# Qwiic_Power_Switch.net
KiCad netlist of a schematic drawn in EAGLE
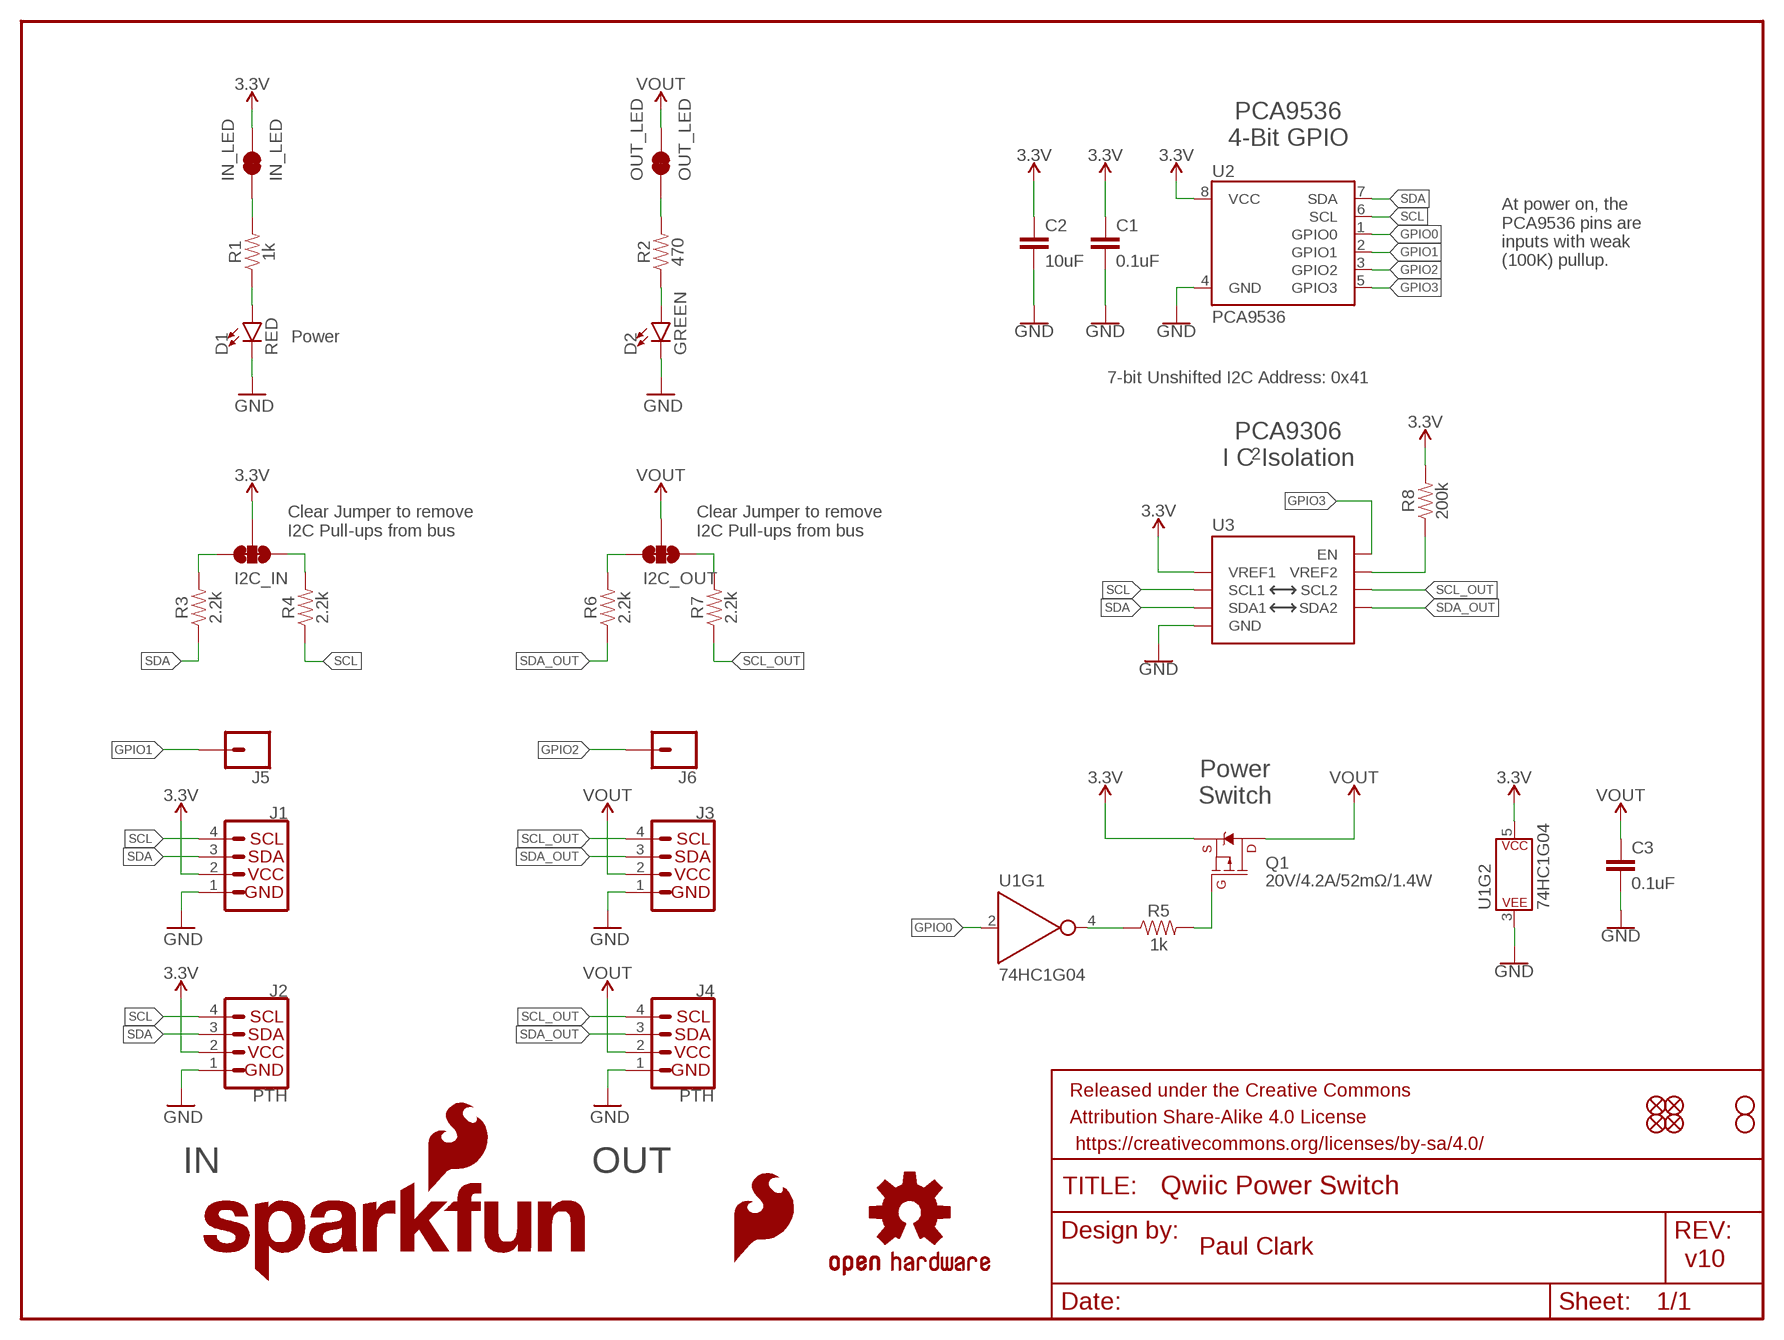
[diagram p0: schematic, sheet 1]

(export (version "E")
  (design (tool "Eeschema 10.0.6"))
  (components
    (comp (ref "C1")
      (value "0.1uF")
      (footprint "eagle-import:0603")
      (libsource (lib "eagle-import") (part "0.1UF-0603-25V-(+80/-20%)"))
    )
    (comp (ref "C2")
      (value "10uF")
      (footprint "eagle-import:0603")
      (libsource (lib "eagle-import") (part "10UF-0603-6.3V-20%"))
    )
    (comp (ref "C3")
      (value "0.1uF")
      (footprint "eagle-import:0603")
      (libsource (lib "eagle-import") (part "0.1UF-0603-25V-(+80/-20%)"))
    )
    (comp (ref "D1")
      (value "RED")
      (footprint "eagle-import:LED-0603")
      (libsource (lib "eagle-import") (part "LED-RED0603"))
    )
    (comp (ref "D2")
      (value "GREEN")
      (footprint "eagle-import:LED-0603")
      (libsource (lib "eagle-import") (part "LED-GREEN0603"))
    )
    (comp (ref "FRAME1")
      (value "FRAME-LETTER")
      (footprint "eagle-import:CREATIVE_COMMONS")
      (libsource (lib "eagle-import") (part "FRAME-LETTER"))
    )
    (comp (ref "I2C_IN")
      (value "JUMPER-SMT_3_2-NC_TRACE_SILK")
      (footprint "eagle-import:SMT-JUMPER_3_2-NC_TRACE_SILK")
      (libsource (lib "eagle-import") (part "JUMPER-SMT_3_2-NC_TRACE_SILK"))
    )
    (comp (ref "I2C_OUT")
      (value "JUMPER-SMT_3_2-NC_TRACE_SILK")
      (footprint "eagle-import:SMT-JUMPER_3_2-NC_TRACE_SILK")
      (libsource (lib "eagle-import") (part "JUMPER-SMT_3_2-NC_TRACE_SILK"))
    )
    (comp (ref "IN_LED")
      (value "IN_LED")
      (footprint "eagle-import:SMT-JUMPER_2_NC_TRACE_SILK")
      (libsource (lib "eagle-import") (part "JUMPER-SMT_2_NC_TRACE_SILK"))
    )
    (comp (ref "J1")
      (value "Qwiic Right Angle")
      (footprint "eagle-import:JST04_1MM_RA")
      (libsource (lib "eagle-import") (part "I2C_STANDARDQWIIC"))
    )
    (comp (ref "J2")
      (value "PTH")
      (footprint "eagle-import:1X04_NO_SILK")
      (libsource (lib "eagle-import") (part "I2C_STANDARD_NO_SILK"))
    )
    (comp (ref "J3")
      (value "Qwiic Right Angle")
      (footprint "eagle-import:JST04_1MM_RA")
      (libsource (lib "eagle-import") (part "I2C_STANDARDQWIIC"))
    )
    (comp (ref "J4")
      (value "PTH")
      (footprint "eagle-import:1X04_NO_SILK")
      (libsource (lib "eagle-import") (part "I2C_STANDARD_NO_SILK"))
    )
    (comp (ref "J5")
      (value "CONN_01PTH_NO_SILK_YES_STOP")
      (footprint "eagle-import:1X01_NO_SILK")
      (libsource (lib "eagle-import") (part "CONN_01PTH_NO_SILK_YES_STOP"))
    )
    (comp (ref "J6")
      (value "CONN_01PTH_NO_SILK_YES_STOP")
      (footprint "eagle-import:1X01_NO_SILK")
      (libsource (lib "eagle-import") (part "CONN_01PTH_NO_SILK_YES_STOP"))
    )
    (comp (ref "JP1")
      (value "FIDUCIAL1X2")
      (footprint "eagle-import:FIDUCIAL-1X2")
      (libsource (lib "eagle-import") (part "FIDUCIAL1X2"))
    )
    (comp (ref "JP2")
      (value "FIDUCIAL1X2")
      (footprint "eagle-import:FIDUCIAL-1X2")
      (libsource (lib "eagle-import") (part "FIDUCIAL1X2"))
    )
    (comp (ref "JP3")
      (value "STAND-OFF")
      (footprint "eagle-import:STAND-OFF")
      (libsource (lib "eagle-import") (part "STAND-OFF"))
    )
    (comp (ref "JP4")
      (value "STAND-OFF")
      (footprint "eagle-import:STAND-OFF")
      (libsource (lib "eagle-import") (part "STAND-OFF"))
    )
    (comp (ref "JP5")
      (value "FIDUCIAL1X2")
      (footprint "eagle-import:FIDUCIAL-1X2")
      (libsource (lib "eagle-import") (part "FIDUCIAL1X2"))
    )
    (comp (ref "JP6")
      (value "FIDUCIAL1X2")
      (footprint "eagle-import:FIDUCIAL-1X2")
      (libsource (lib "eagle-import") (part "FIDUCIAL1X2"))
    )
    (comp (ref "LOGO1")
      (value "OSHW-LOGOMINI")
      (footprint "eagle-import:OSHW-LOGO-MINI")
      (libsource (lib "eagle-import") (part "OSHW-LOGOMINI"))
    )
    (comp (ref "LOGO2")
      (value "SFE_LOGO_FLAME.1_INCH")
      (footprint "eagle-import:SFE_LOGO_FLAME_.1")
      (libsource (lib "eagle-import") (part "SFE_LOGO_FLAME.1_INCH"))
    )
    (comp (ref "LOGO3")
      (value "SFE_LOGO_NAME_FLAME.1_INCH")
      (footprint "eagle-import:SFE_LOGO_NAME_FLAME_.1")
      (libsource (lib "eagle-import") (part "SFE_LOGO_NAME_FLAME.1_INCH"))
    )
    (comp (ref "OUT_LED")
      (value "OUT_LED")
      (footprint "eagle-import:SMT-JUMPER_2_NC_TRACE_SILK")
      (libsource (lib "eagle-import") (part "JUMPER-SMT_2_NC_TRACE_SILK"))
    )
    (comp (ref "Q1")
      (value "20V/4.2A/52mΩ/1.4W")
      (footprint "eagle-import:SOT23-3")
      (libsource (lib "eagle-import") (part "MOSFET_PCH-DMG2305UX-7"))
    )
    (comp (ref "R1")
      (value "1k")
      (footprint "eagle-import:0603")
      (libsource (lib "eagle-import") (part "1KOHM-0603-1/10W-1%"))
    )
    (comp (ref "R2")
      (value "470")
      (footprint "eagle-import:0603")
      (libsource (lib "eagle-import") (part "470OHM-0603-1/10W-1%"))
    )
    (comp (ref "R3")
      (value "2.2k")
      (footprint "eagle-import:0603")
      (libsource (lib "eagle-import") (part "2.2KOHM-0603-1/10W-1%"))
    )
    (comp (ref "R4")
      (value "2.2k")
      (footprint "eagle-import:0603")
      (libsource (lib "eagle-import") (part "2.2KOHM-0603-1/10W-1%"))
    )
    (comp (ref "R5")
      (value "1k")
      (footprint "eagle-import:0603")
      (libsource (lib "eagle-import") (part "1KOHM-0603-1/10W-1%"))
    )
    (comp (ref "R6")
      (value "2.2k")
      (footprint "eagle-import:0603")
      (libsource (lib "eagle-import") (part "2.2KOHM-0603-1/10W-1%"))
    )
    (comp (ref "R7")
      (value "2.2k")
      (footprint "eagle-import:0603")
      (libsource (lib "eagle-import") (part "2.2KOHM-0603-1/10W-1%"))
    )
    (comp (ref "R8")
      (value "200k")
      (footprint "eagle-import:0603")
      (libsource (lib "eagle-import") (part "200KOHM-0603-1/10W-1%"))
    )
    (comp (ref "U1")
      (value "74HC1G04")
      (footprint "eagle-import:SOT353")
      (libsource (lib "eagle-import") (part "741G04HC"))
    )
    (comp (ref "U2")
      (value "PCA9536")
      (footprint "eagle-import:MSOP8")
      (libsource (lib "eagle-import") (part "PCA9536"))
    )
    (comp (ref "U3")
      (value "PCA9306VSSOP_8PIN")
      (footprint "eagle-import:VSSOP_8PIN")
      (libsource (lib "eagle-import") (part "PCA9306VSSOP_8PIN"))
    )
  )
  (nets
    (net (code "1") (name "3.3V") (class "Default")
      (node (ref "C1") (pin "1") (pinfunction "1_1") (pintype "passive"))
      (node (ref "C2") (pin "1") (pinfunction "1_1") (pintype "passive"))
      (node (ref "I2C_IN") (pin "2") (pinfunction "2_2") (pintype "passive"))
      (node (ref "IN_LED") (pin "2") (pinfunction "2_2") (pintype "passive"))
      (node (ref "J1") (pin "2") (pinfunction "2_2") (pintype "power_in"))
      (node (ref "J2") (pin "2") (pinfunction "2_2") (pintype "power_in"))
      (node (ref "Q1") (pin "2") (pinfunction "S_2") (pintype "bidirectional"))
      (node (ref "R8") (pin "2") (pinfunction "2_2") (pintype "passive"))
      (node (ref "U1") (pin "5") (pinfunction "P$V+_5") (pintype "bidirectional"))
      (node (ref "U2") (pin "8") (pinfunction "VCC_8") (pintype "bidirectional"))
      (node (ref "U3") (pin "P2") (pinfunction "VREF1_P2") (pintype "power_in"))
    )
    (net (code "2") (name "GND") (class "Default")
      (node (ref "C1") (pin "2") (pinfunction "2_2") (pintype "passive"))
      (node (ref "C2") (pin "2") (pinfunction "2_2") (pintype "passive"))
      (node (ref "C3") (pin "2") (pinfunction "2_2") (pintype "passive"))
      (node (ref "D1") (pin "C") (pinfunction "C_C") (pintype "passive"))
      (node (ref "D2") (pin "C") (pinfunction "C_C") (pintype "passive"))
      (node (ref "J1") (pin "1") (pinfunction "1_1") (pintype "power_in"))
      (node (ref "J2") (pin "1") (pinfunction "1_1") (pintype "power_in"))
      (node (ref "J3") (pin "1") (pinfunction "1_1") (pintype "power_in"))
      (node (ref "J4") (pin "1") (pinfunction "1_1") (pintype "power_in"))
      (node (ref "U1") (pin "3") (pinfunction "P$V-_3") (pintype "bidirectional"))
      (node (ref "U2") (pin "4") (pinfunction "GND_4") (pintype "bidirectional"))
      (node (ref "U3") (pin "P1") (pinfunction "GND_P1") (pintype "power_in"))
    )
    (net (code "3") (name "GPIO0") (class "Default")
      (node (ref "U1") (pin "2") (pinfunction "A_2") (pintype "bidirectional"))
      (node (ref "U2") (pin "1") (pinfunction "GPIO0_1") (pintype "bidirectional"))
    )
    (net (code "4") (name "GPIO1") (class "Default")
      (node (ref "J5") (pin "1") (pinfunction "1_1") (pintype "passive"))
      (node (ref "U2") (pin "2") (pinfunction "GPIO1_2") (pintype "bidirectional"))
    )
    (net (code "5") (name "GPIO2") (class "Default")
      (node (ref "J6") (pin "1") (pinfunction "1_1") (pintype "passive"))
      (node (ref "U2") (pin "3") (pinfunction "GPIO2_3") (pintype "bidirectional"))
    )
    (net (code "6") (name "GPIO3") (class "Default")
      (node (ref "U2") (pin "5") (pinfunction "GPIO3_5") (pintype "bidirectional"))
      (node (ref "U3") (pin "P8") (pinfunction "EN_P8") (pintype "input"))
    )
    (net (code "7") (name "Net-(D1-PadA)") (class "Default")
      (node (ref "D1") (pin "A") (pinfunction "A_A") (pintype "passive"))
      (node (ref "R1") (pin "1") (pinfunction "1_1") (pintype "passive"))
    )
    (net (code "8") (name "Net-(D2-PadA)") (class "Default")
      (node (ref "D2") (pin "A") (pinfunction "A_A") (pintype "passive"))
      (node (ref "R2") (pin "1") (pinfunction "1_1") (pintype "passive"))
    )
    (net (code "9") (name "Net-(I2C_IN-Pad1)") (class "Default")
      (node (ref "I2C_IN") (pin "1") (pinfunction "1_1") (pintype "passive"))
      (node (ref "R4") (pin "2") (pinfunction "2_2") (pintype "passive"))
    )
    (net (code "10") (name "Net-(I2C_IN-Pad3)") (class "Default")
      (node (ref "I2C_IN") (pin "3") (pinfunction "3_3") (pintype "passive"))
      (node (ref "R3") (pin "2") (pinfunction "2_2") (pintype "passive"))
    )
    (net (code "11") (name "Net-(I2C_OUT-Pad1)") (class "Default")
      (node (ref "I2C_OUT") (pin "1") (pinfunction "1_1") (pintype "passive"))
      (node (ref "R7") (pin "2") (pinfunction "2_2") (pintype "passive"))
    )
    (net (code "12") (name "Net-(I2C_OUT-Pad3)") (class "Default")
      (node (ref "I2C_OUT") (pin "3") (pinfunction "3_3") (pintype "passive"))
      (node (ref "R6") (pin "2") (pinfunction "2_2") (pintype "passive"))
    )
    (net (code "13") (name "Net-(IN_LED-Pad1)") (class "Default")
      (node (ref "IN_LED") (pin "1") (pinfunction "1_1") (pintype "passive"))
      (node (ref "R1") (pin "2") (pinfunction "2_2") (pintype "passive"))
    )
    (net (code "14") (name "Net-(OUT_LED-Pad1)") (class "Default")
      (node (ref "OUT_LED") (pin "1") (pinfunction "1_1") (pintype "passive"))
      (node (ref "R2") (pin "2") (pinfunction "2_2") (pintype "passive"))
    )
    (net (code "15") (name "Net-(Q1-G)") (class "Default")
      (node (ref "Q1") (pin "1") (pinfunction "G_1") (pintype "bidirectional"))
      (node (ref "R5") (pin "2") (pinfunction "2_2") (pintype "passive"))
    )
    (net (code "16") (name "Net-(U1A-Y)") (class "Default")
      (node (ref "R5") (pin "1") (pinfunction "1_1") (pintype "passive"))
      (node (ref "U1") (pin "4") (pinfunction "Y_4") (pintype "bidirectional"))
    )
    (net (code "17") (name "Net-(U3-VREF2)") (class "Default")
      (node (ref "R8") (pin "1") (pinfunction "1_1") (pintype "passive"))
      (node (ref "U3") (pin "P7") (pinfunction "VREF2_P7") (pintype "power_in"))
    )
    (net (code "18") (name "SCL") (class "Default")
      (node (ref "J1") (pin "4") (pinfunction "4_4") (pintype "passive"))
      (node (ref "J2") (pin "4") (pinfunction "4_4") (pintype "passive"))
      (node (ref "R4") (pin "1") (pinfunction "1_1") (pintype "passive"))
      (node (ref "U2") (pin "6") (pinfunction "SCL_6") (pintype "bidirectional"))
      (node (ref "U3") (pin "P3") (pinfunction "SCL1_P3") (pintype "bidirectional"))
    )
    (net (code "19") (name "SCL_OUT") (class "Default")
      (node (ref "J3") (pin "4") (pinfunction "4_4") (pintype "passive"))
      (node (ref "J4") (pin "4") (pinfunction "4_4") (pintype "passive"))
      (node (ref "R7") (pin "1") (pinfunction "1_1") (pintype "passive"))
      (node (ref "U3") (pin "P6") (pinfunction "SCL2_P6") (pintype "bidirectional"))
    )
    (net (code "20") (name "SDA") (class "Default")
      (node (ref "J1") (pin "3") (pinfunction "3_3") (pintype "passive"))
      (node (ref "J2") (pin "3") (pinfunction "3_3") (pintype "passive"))
      (node (ref "R3") (pin "1") (pinfunction "1_1") (pintype "passive"))
      (node (ref "U2") (pin "7") (pinfunction "SDA_7") (pintype "bidirectional"))
      (node (ref "U3") (pin "P4") (pinfunction "SDA1_P4") (pintype "bidirectional"))
    )
    (net (code "21") (name "SDA_OUT") (class "Default")
      (node (ref "J3") (pin "3") (pinfunction "3_3") (pintype "passive"))
      (node (ref "J4") (pin "3") (pinfunction "3_3") (pintype "passive"))
      (node (ref "R6") (pin "1") (pinfunction "1_1") (pintype "passive"))
      (node (ref "U3") (pin "P5") (pinfunction "SDA2_P5") (pintype "bidirectional"))
    )
    (net (code "22") (name "VOUT") (class "Default")
      (node (ref "C3") (pin "1") (pinfunction "1_1") (pintype "passive"))
      (node (ref "I2C_OUT") (pin "2") (pinfunction "2_2") (pintype "passive"))
      (node (ref "J3") (pin "2") (pinfunction "2_2") (pintype "power_in"))
      (node (ref "J4") (pin "2") (pinfunction "2_2") (pintype "power_in"))
      (node (ref "OUT_LED") (pin "2") (pinfunction "2_2") (pintype "passive"))
      (node (ref "Q1") (pin "3") (pinfunction "D_3") (pintype "bidirectional"))
    )
  )
)
